# Main.net
KiCad netlist of a schematic drawn in Altium Designer
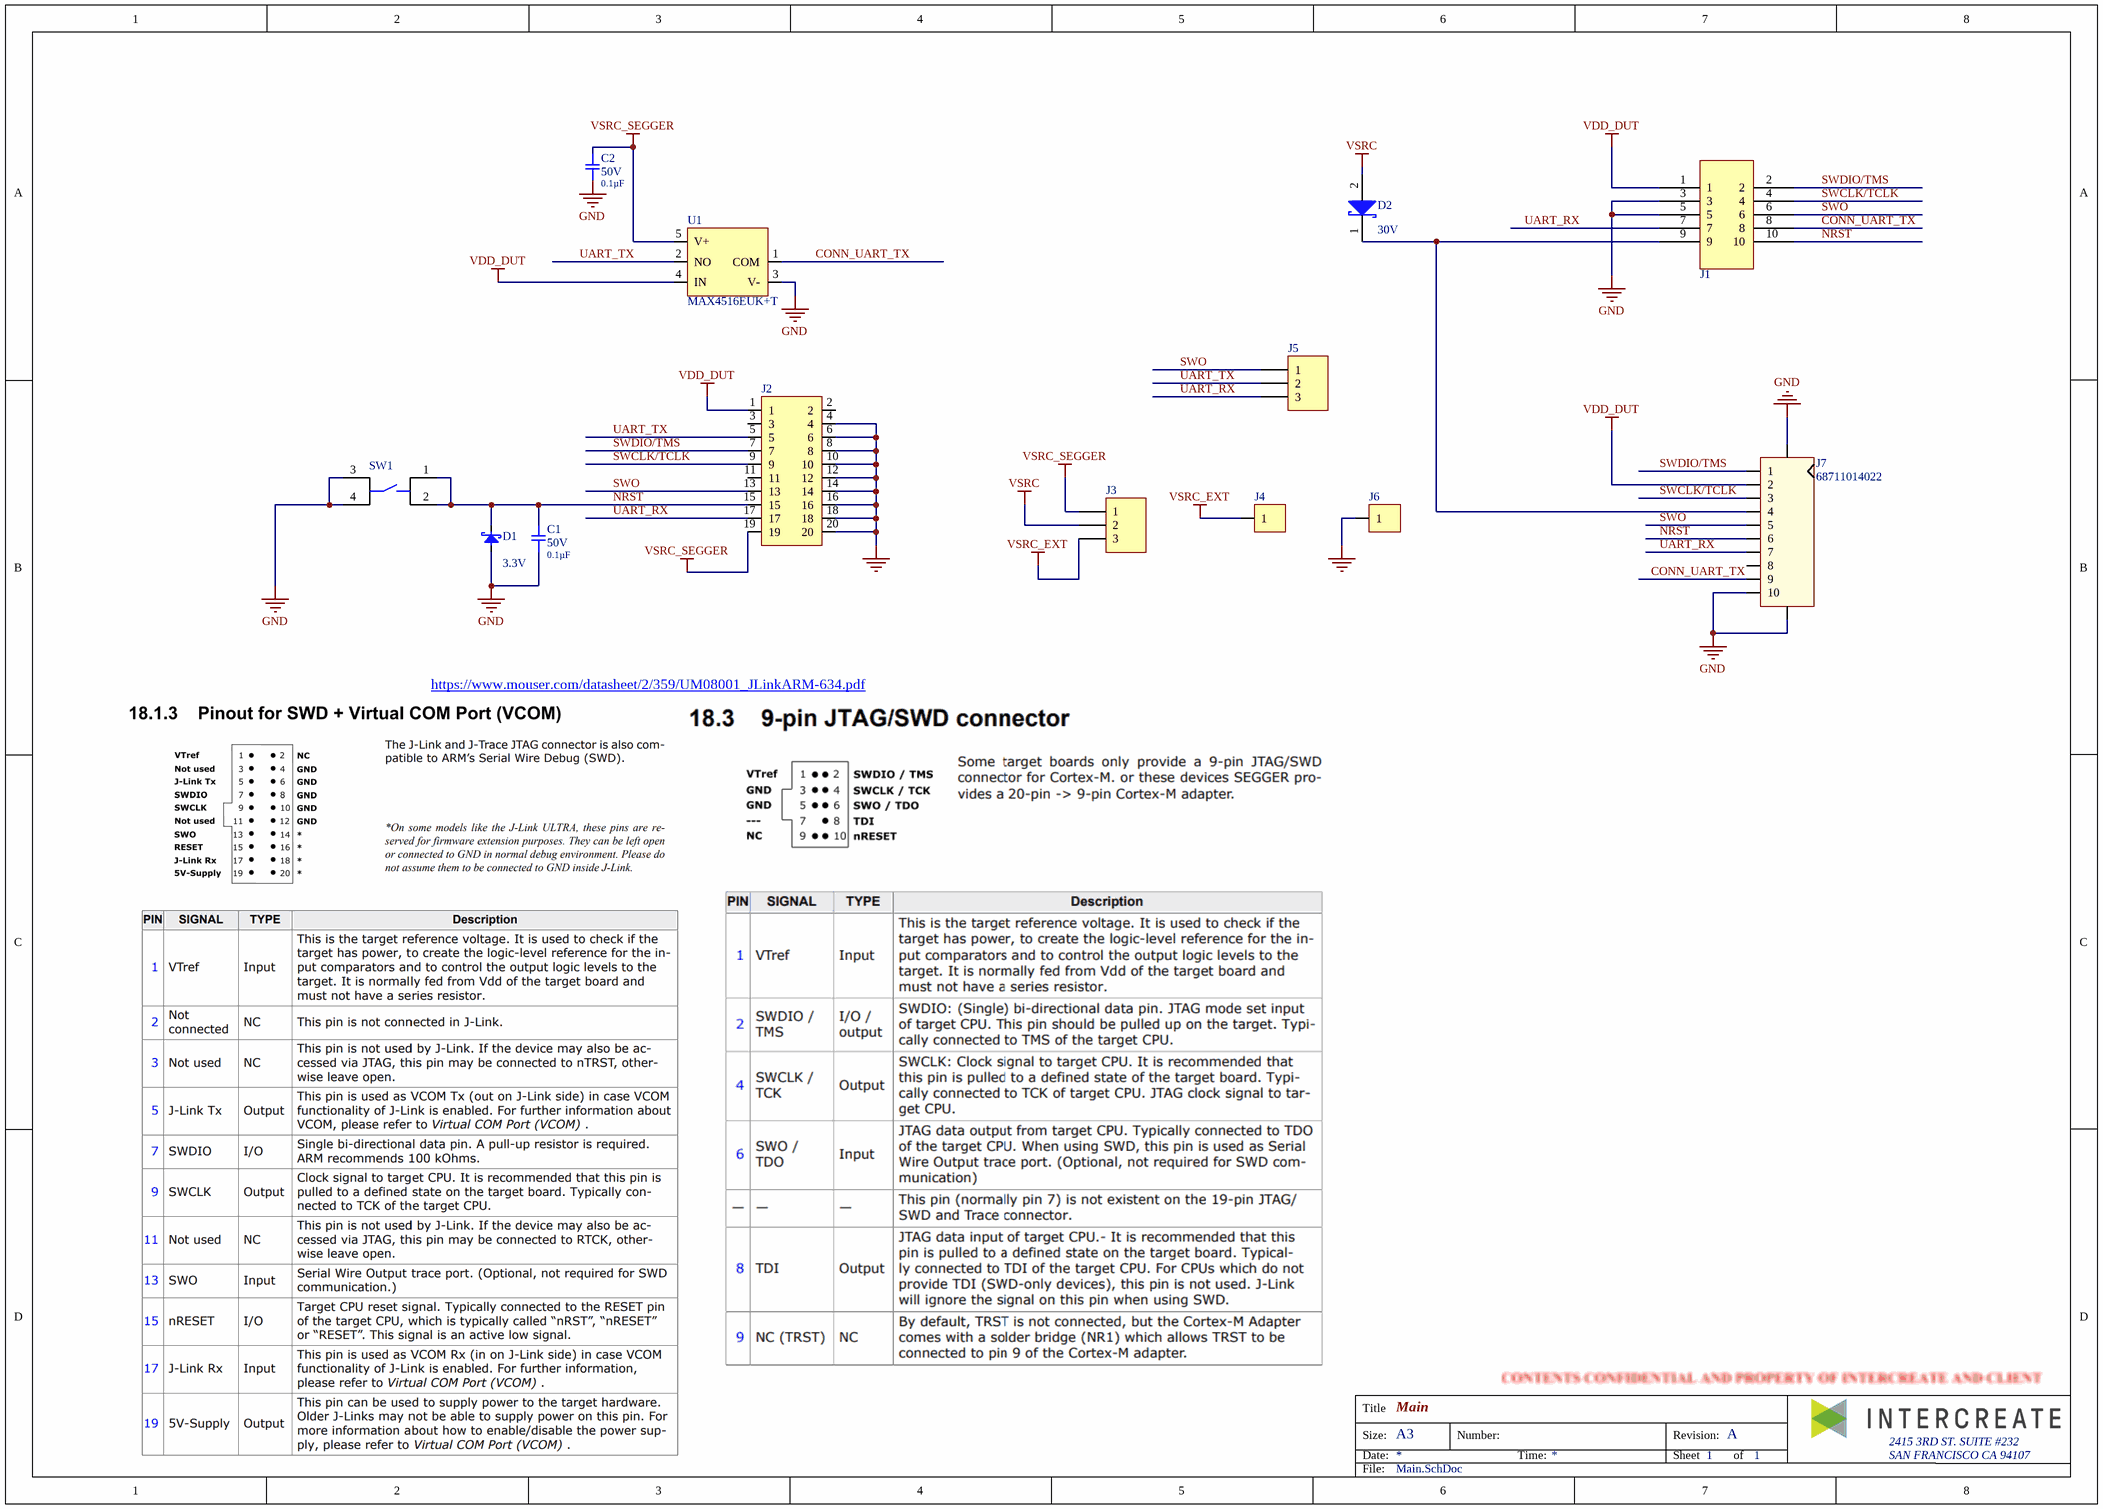
[diagram p0: Main.SchDoc]

(export (version "E")
  (design (tool "Eeschema 10.0.6"))
  (components
    (comp (ref "C1")
      (value "0.1µF")
      (footprint "CAP-0402")
      (description "CAP CER 0.1UF 50V X7R 0402 10%")
      (fields
        (field (name "TOLERANCE") "10%")
        (field (name "VOLTAGE RATING") "50V")
        (field (name "Comment") "GCM155R71H104KE02D")
      )
      (libsource (lib "intercreate") (part "CAP-0.1uF-50V-0402"))
    )
    (comp (ref "C2")
      (value "0.1µF")
      (footprint "CAP-0402")
      (description "CAP CER 0.1UF 50V X7R 0402 10%")
      (fields
        (field (name "TOLERANCE") "10%")
        (field (name "VOLTAGE RATING") "50V")
        (field (name "Comment") "GCM155R71H104KE02D")
      )
      (libsource (lib "intercreate") (part "CAP-0.1uF-50V-0402"))
    )
    (comp (ref "D1")
      (value "CPDQ3V3U-HF")
      (footprint "DIODE-SOD923f")
      (description "TVS DIODE 3.3V 10.4V SOD923F")
      (fields (field (name "REVERSE STANDOFF VOLTAGE") "3.3V"))
      (libsource (lib "intercreate") (part "DIODE-TVS-3.3V-SOD923F"))
    )
    (comp (ref "D2")
      (value "PMEG3010EP,115")
      (footprint "DIODE-SOD128")
      (description "DIODE SCHOTTKY 30V 1A SOD128")
      (fields (field (name "BASE PART NUMBER") "PMEG3010") (field (name "REVERSE VOLTAGE") "30V"))
      (libsource (lib "diodes") (part "DIODE-SCHOTTKY-30V-1A-SOD128"))
    )
    (comp (ref "J1")
      (value "FTSH-105-01-L-DV-K")
      (footprint "HDR-V-2X5-M")
      (description "CONN HEADER 10 POS DUAL .05\" SMD")
      (fields (field (name "MANUFACTURER") "Samtec"))
      (libsource (lib "intercreate") (part "HDR-V-2X5-M-JTAG"))
    )
    (comp (ref "J2")
      (value "SFH11-PBPC-D10-ST-BK")
      (footprint "HDR-V-2X10-F-2.54MM")
      (description "20 Position Header Connector 0.100\" (2.54mm) Through Hole Gold")
      (libsource (lib "intercreate") (part "HDR-V-2X10-F-2.54MM"))
    )
    (comp (ref "J3")
      (value "61300311121")
      (footprint "HDR-V-1X3")
      (description "Header, 3-Pin, 0.1\"")
      (fields (field (name "MANUFACTURER") "Wurth Electronics") (field (name "PUBLISHER") "Altium Limited"))
      (libsource (lib "intercreate") (part "HDR-V-1X3-M"))
    )
    (comp (ref "J4")
      (value "75160-101-01LF")
      (footprint "HDR-V-1X1-M")
      (libsource (lib "intercreate") (part "HDR-V-1X1-M"))
    )
    (comp (ref "J5")
      (value "61300311121")
      (footprint "HDR-V-1X3")
      (description "Header, 3-Pin, 0.1\"")
      (fields (field (name "MANUFACTURER") "Wurth Electronics") (field (name "PUBLISHER") "Altium Limited"))
      (libsource (lib "intercreate") (part "HDR-V-1X3-M"))
    )
    (comp (ref "J6")
      (value "75160-101-01LF")
      (footprint "HDR-V-1X1-M")
      (libsource (lib "intercreate") (part "HDR-V-1X1-M"))
    )
    (comp (ref "J7")
      (value "68711014022")
      (footprint "CONN-R-FPC-10P-WURTH")
      (description "CONN FFC FPC 10POS 0.50MM RA")
      (libsource (lib "intercreate") (part "CONN-R-FPC-10P-0.5MM-WURTH"))
    )
    (comp (ref "SW1")
      (value "PTS645SK50SMTR92 LFS")
      (footprint "BTN-SPST-PTS645SK50SMTR92")
      (description "C & K COMPONENTS - PTS645SK50SMTR92LFS - SWITCH, SPST, 0.05A, 12VDC, SMD, 5MM")
      (libsource (lib "intercreate") (part "BTN-SPST-PTS645SK50SMTR92"))
    )
    (comp (ref "U1")
      (value "MAX4516EUK+T")
      (footprint "IC-SOT-23-5")
      (description "MAX4516 Series SPST-NO 6V 20 Ohm SMT Analog Switch - SOT-23")
      (libsource (lib "intercreate") (part "IC-SW-MAX4516"))
    )
  )
  (nets
    (net (code "1") (name "/CONN_UART_TX") (class "Default")
      (node (ref "J1") (pin "8") (pinfunction "8_8") (pintype "passive"))
      (node (ref "J7") (pin "9") (pinfunction "9_9") (pintype "passive"))
      (node (ref "U1") (pin "1") (pinfunction "COM_1") (pintype "passive"))
    )
    (net (code "2") (name "/NRST") (class "Default")
      (node (ref "C1") (pin "2") (pinfunction "2_2") (pintype "passive"))
      (node (ref "D1") (pin "1") (pinfunction "K_1") (pintype "passive"))
      (node (ref "J1") (pin "10") (pinfunction "10_10") (pintype "passive"))
      (node (ref "J2") (pin "15") (pinfunction "15_15") (pintype "passive"))
      (node (ref "J7") (pin "6") (pinfunction "6_6") (pintype "passive"))
      (node (ref "SW1") (pin "1") (pinfunction "1_1") (pintype "passive"))
      (node (ref "SW1") (pin "2") (pinfunction "2_2") (pintype "passive"))
    )
    (net (code "3") (name "/SWCLK{slash}TCLK") (class "Default")
      (node (ref "J1") (pin "4") (pinfunction "4_4") (pintype "passive"))
      (node (ref "J2") (pin "9") (pinfunction "9_9") (pintype "passive"))
      (node (ref "J7") (pin "3") (pinfunction "3_3") (pintype "passive"))
    )
    (net (code "4") (name "/SWDIO{slash}TMS") (class "Default")
      (node (ref "J1") (pin "2") (pinfunction "2_2") (pintype "passive"))
      (node (ref "J2") (pin "7") (pinfunction "7_7") (pintype "passive"))
      (node (ref "J7") (pin "1") (pinfunction "1_1") (pintype "passive"))
    )
    (net (code "5") (name "/SWO") (class "Default")
      (node (ref "J1") (pin "6") (pinfunction "6_6") (pintype "passive"))
      (node (ref "J2") (pin "13") (pinfunction "13_13") (pintype "passive"))
      (node (ref "J5") (pin "1") (pinfunction "1_1") (pintype "passive"))
      (node (ref "J7") (pin "5") (pinfunction "5_5") (pintype "passive"))
    )
    (net (code "6") (name "/UART_RX") (class "Default")
      (node (ref "J1") (pin "7") (pinfunction "7_7") (pintype "passive"))
      (node (ref "J2") (pin "17") (pinfunction "17_17") (pintype "passive"))
      (node (ref "J5") (pin "3") (pinfunction "3_3") (pintype "passive"))
      (node (ref "J7") (pin "7") (pinfunction "7_7") (pintype "passive"))
    )
    (net (code "7") (name "/UART_TX") (class "Default")
      (node (ref "J2") (pin "5") (pinfunction "5_5") (pintype "passive"))
      (node (ref "J5") (pin "2") (pinfunction "2_2") (pintype "passive"))
      (node (ref "U1") (pin "2") (pinfunction "NO_2") (pintype "passive"))
    )
    (net (code "8") (name "GND") (class "Default")
      (node (ref "C1") (pin "1") (pinfunction "1_1") (pintype "passive"))
      (node (ref "C2") (pin "1") (pinfunction "1_1") (pintype "passive"))
      (node (ref "D1") (pin "2") (pinfunction "A_2") (pintype "passive"))
      (node (ref "J1") (pin "3") (pinfunction "3_3") (pintype "passive"))
      (node (ref "J1") (pin "5") (pinfunction "5_5") (pintype "passive"))
      (node (ref "J2") (pin "10") (pinfunction "10_10") (pintype "passive"))
      (node (ref "J2") (pin "12") (pinfunction "12_12") (pintype "passive"))
      (node (ref "J2") (pin "14") (pinfunction "14_14") (pintype "passive"))
      (node (ref "J2") (pin "16") (pinfunction "16_16") (pintype "passive"))
      (node (ref "J2") (pin "18") (pinfunction "18_18") (pintype "passive"))
      (node (ref "J2") (pin "20") (pinfunction "20_20") (pintype "passive"))
      (node (ref "J2") (pin "4") (pinfunction "4_4") (pintype "passive"))
      (node (ref "J2") (pin "6") (pinfunction "6_6") (pintype "passive"))
      (node (ref "J2") (pin "8") (pinfunction "8_8") (pintype "passive"))
      (node (ref "J6") (pin "1") (pinfunction "1_1") (pintype "passive"))
      (node (ref "J7") (pin "10") (pinfunction "10_10") (pintype "passive"))
      (node (ref "J7") (pin "ME1") (pinfunction "ME1_ME1") (pintype "passive"))
      (node (ref "J7") (pin "ME2") (pinfunction "ME2_ME2") (pintype "passive"))
      (node (ref "SW1") (pin "3") (pinfunction "3_3") (pintype "passive"))
      (node (ref "SW1") (pin "4") (pinfunction "4_4") (pintype "passive"))
      (node (ref "U1") (pin "3") (pinfunction "V-_3") (pintype "passive"))
    )
    (net (code "9") (name "Net-(D2-K)") (class "Default")
      (node (ref "D2") (pin "1") (pinfunction "K_1") (pintype "passive"))
      (node (ref "J1") (pin "9") (pinfunction "9_9") (pintype "passive"))
      (node (ref "J7") (pin "4") (pinfunction "4_4") (pintype "passive"))
    )
    (net (code "10") (name "VDD_DUT") (class "Default")
      (node (ref "J1") (pin "1") (pinfunction "1_1") (pintype "passive"))
      (node (ref "J2") (pin "1") (pinfunction "1_1") (pintype "passive"))
      (node (ref "J7") (pin "2") (pinfunction "2_2") (pintype "passive"))
      (node (ref "U1") (pin "4") (pinfunction "IN_4") (pintype "passive"))
    )
    (net (code "11") (name "VSRC") (class "Default")
      (node (ref "D2") (pin "2") (pinfunction "A_2") (pintype "passive"))
      (node (ref "J3") (pin "2") (pinfunction "2_2") (pintype "passive"))
    )
    (net (code "12") (name "VSRC_EXT") (class "Default")
      (node (ref "J3") (pin "3") (pinfunction "3_3") (pintype "passive"))
      (node (ref "J4") (pin "1") (pinfunction "1_1") (pintype "passive"))
    )
    (net (code "13") (name "VSRC_SEGGER") (class "Default")
      (node (ref "C2") (pin "2") (pinfunction "2_2") (pintype "passive"))
      (node (ref "J2") (pin "19") (pinfunction "19_19") (pintype "passive"))
      (node (ref "J3") (pin "1") (pinfunction "1_1") (pintype "passive"))
      (node (ref "U1") (pin "5") (pinfunction "V+_5") (pintype "passive"))
    )
    (net (code "14") (name "unconnected-(J2-Pad2)") (class "Default")
      (node (ref "J2") (pin "2") (pinfunction "2_2") (pintype "passive"))
    )
    (net (code "15") (name "unconnected-(J2-Pad3)") (class "Default")
      (node (ref "J2") (pin "3") (pinfunction "3_3") (pintype "passive"))
    )
    (net (code "16") (name "unconnected-(J2-Pad11)") (class "Default")
      (node (ref "J2") (pin "11") (pinfunction "11_11") (pintype "passive"))
    )
    (net (code "17") (name "unconnected-(J7-Pad8)") (class "Default")
      (node (ref "J7") (pin "8") (pinfunction "8_8") (pintype "passive"))
    )
  )
)
